# JTAG_connector3.net
KiCad netlist of a schematic drawn in Altium Designer
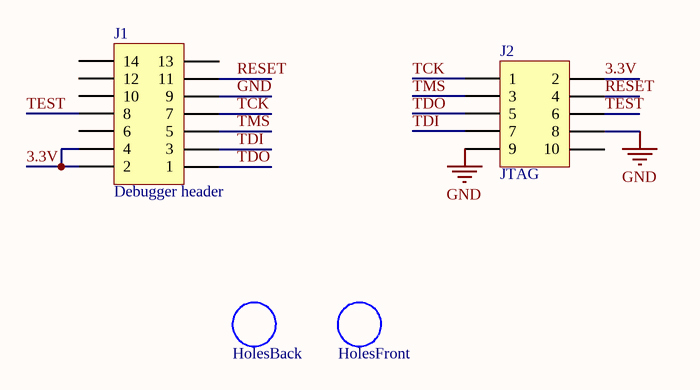
[diagram p0: JTAG_connector3.SchDoc]

(export (version "E")
  (design (tool "Eeschema 10.0.6"))
  (components
    (comp (ref "HolesBack")
      (value "non connect")
      (footprint "3/8\"Caster")
      (description "This is just a space saver to get the caster onto the pcb")
      (libsource (lib "mrone") (part "Caster"))
    )
    (comp (ref "HolesFront")
      (value "non connect")
      (footprint "3/8\"Caster")
      (description "This is just a space saver to get the caster onto the pcb")
      (libsource (lib "mrone") (part "Caster"))
    )
    (comp (ref "J1")
      (value "Debugger header")
      (footprint "HDR2X7")
      (description "Header, 7-Pin, Dual row")
      (fields (field (name "PUBLISHER") "Altium Limited"))
      (libsource (lib "Miscellaneous Connectors") (part "Header 7X2"))
    )
    (comp (ref "J2")
      (value "JTAG")
      (footprint "HDR2X5")
      (description "Header, 5-Pin, Dual row")
      (fields (field (name "PUBLISHER") "Altium Limited"))
      (libsource (lib "Miscellaneous Connectors") (part "Header 5X2"))
    )
  )
  (nets
    (net (code "1") (name "/3.3V") (class "Default")
      (node (ref "J1") (pin "2") (pinfunction "2_2") (pintype "passive"))
      (node (ref "J1") (pin "4") (pinfunction "4_4") (pintype "passive"))
      (node (ref "J2") (pin "2") (pinfunction "2_2") (pintype "passive"))
    )
    (net (code "2") (name "/RESET") (class "Default")
      (node (ref "J1") (pin "11") (pinfunction "11_11") (pintype "passive"))
      (node (ref "J2") (pin "4") (pinfunction "4_4") (pintype "passive"))
    )
    (net (code "3") (name "/TCK") (class "Default")
      (node (ref "J1") (pin "7") (pinfunction "7_7") (pintype "passive"))
      (node (ref "J2") (pin "1") (pinfunction "1_1") (pintype "passive"))
    )
    (net (code "4") (name "/TDI") (class "Default")
      (node (ref "J1") (pin "3") (pinfunction "3_3") (pintype "passive"))
      (node (ref "J2") (pin "7") (pinfunction "7_7") (pintype "passive"))
    )
    (net (code "5") (name "/TDO") (class "Default")
      (node (ref "J1") (pin "1") (pinfunction "1_1") (pintype "passive"))
      (node (ref "J2") (pin "5") (pinfunction "5_5") (pintype "passive"))
    )
    (net (code "6") (name "/TEST") (class "Default")
      (node (ref "J1") (pin "8") (pinfunction "8_8") (pintype "passive"))
      (node (ref "J2") (pin "6") (pinfunction "6_6") (pintype "passive"))
    )
    (net (code "7") (name "/TMS") (class "Default")
      (node (ref "J1") (pin "5") (pinfunction "5_5") (pintype "passive"))
      (node (ref "J2") (pin "3") (pinfunction "3_3") (pintype "passive"))
    )
    (net (code "8") (name "GND") (class "Default")
      (node (ref "J1") (pin "9") (pinfunction "9_9") (pintype "passive"))
      (node (ref "J2") (pin "8") (pinfunction "8_8") (pintype "passive"))
      (node (ref "J2") (pin "9") (pinfunction "9_9") (pintype "passive"))
    )
    (net (code "9") (name "unconnected-(J1-Pad6)") (class "Default")
      (node (ref "J1") (pin "6") (pinfunction "6_6") (pintype "passive"))
    )
    (net (code "10") (name "unconnected-(J1-Pad10)") (class "Default")
      (node (ref "J1") (pin "10") (pinfunction "10_10") (pintype "passive"))
    )
    (net (code "11") (name "unconnected-(J1-Pad12)") (class "Default")
      (node (ref "J1") (pin "12") (pinfunction "12_12") (pintype "passive"))
    )
    (net (code "12") (name "unconnected-(J1-Pad13)") (class "Default")
      (node (ref "J1") (pin "13") (pinfunction "13_13") (pintype "passive"))
    )
    (net (code "13") (name "unconnected-(J1-Pad14)") (class "Default")
      (node (ref "J1") (pin "14") (pinfunction "14_14") (pintype "passive"))
    )
    (net (code "14") (name "unconnected-(J2-Pad10)") (class "Default")
      (node (ref "J2") (pin "10") (pinfunction "10_10") (pintype "passive"))
    )
  )
)
